# counter_module.net
KiCad netlist of a schematic drawn in EAGLE
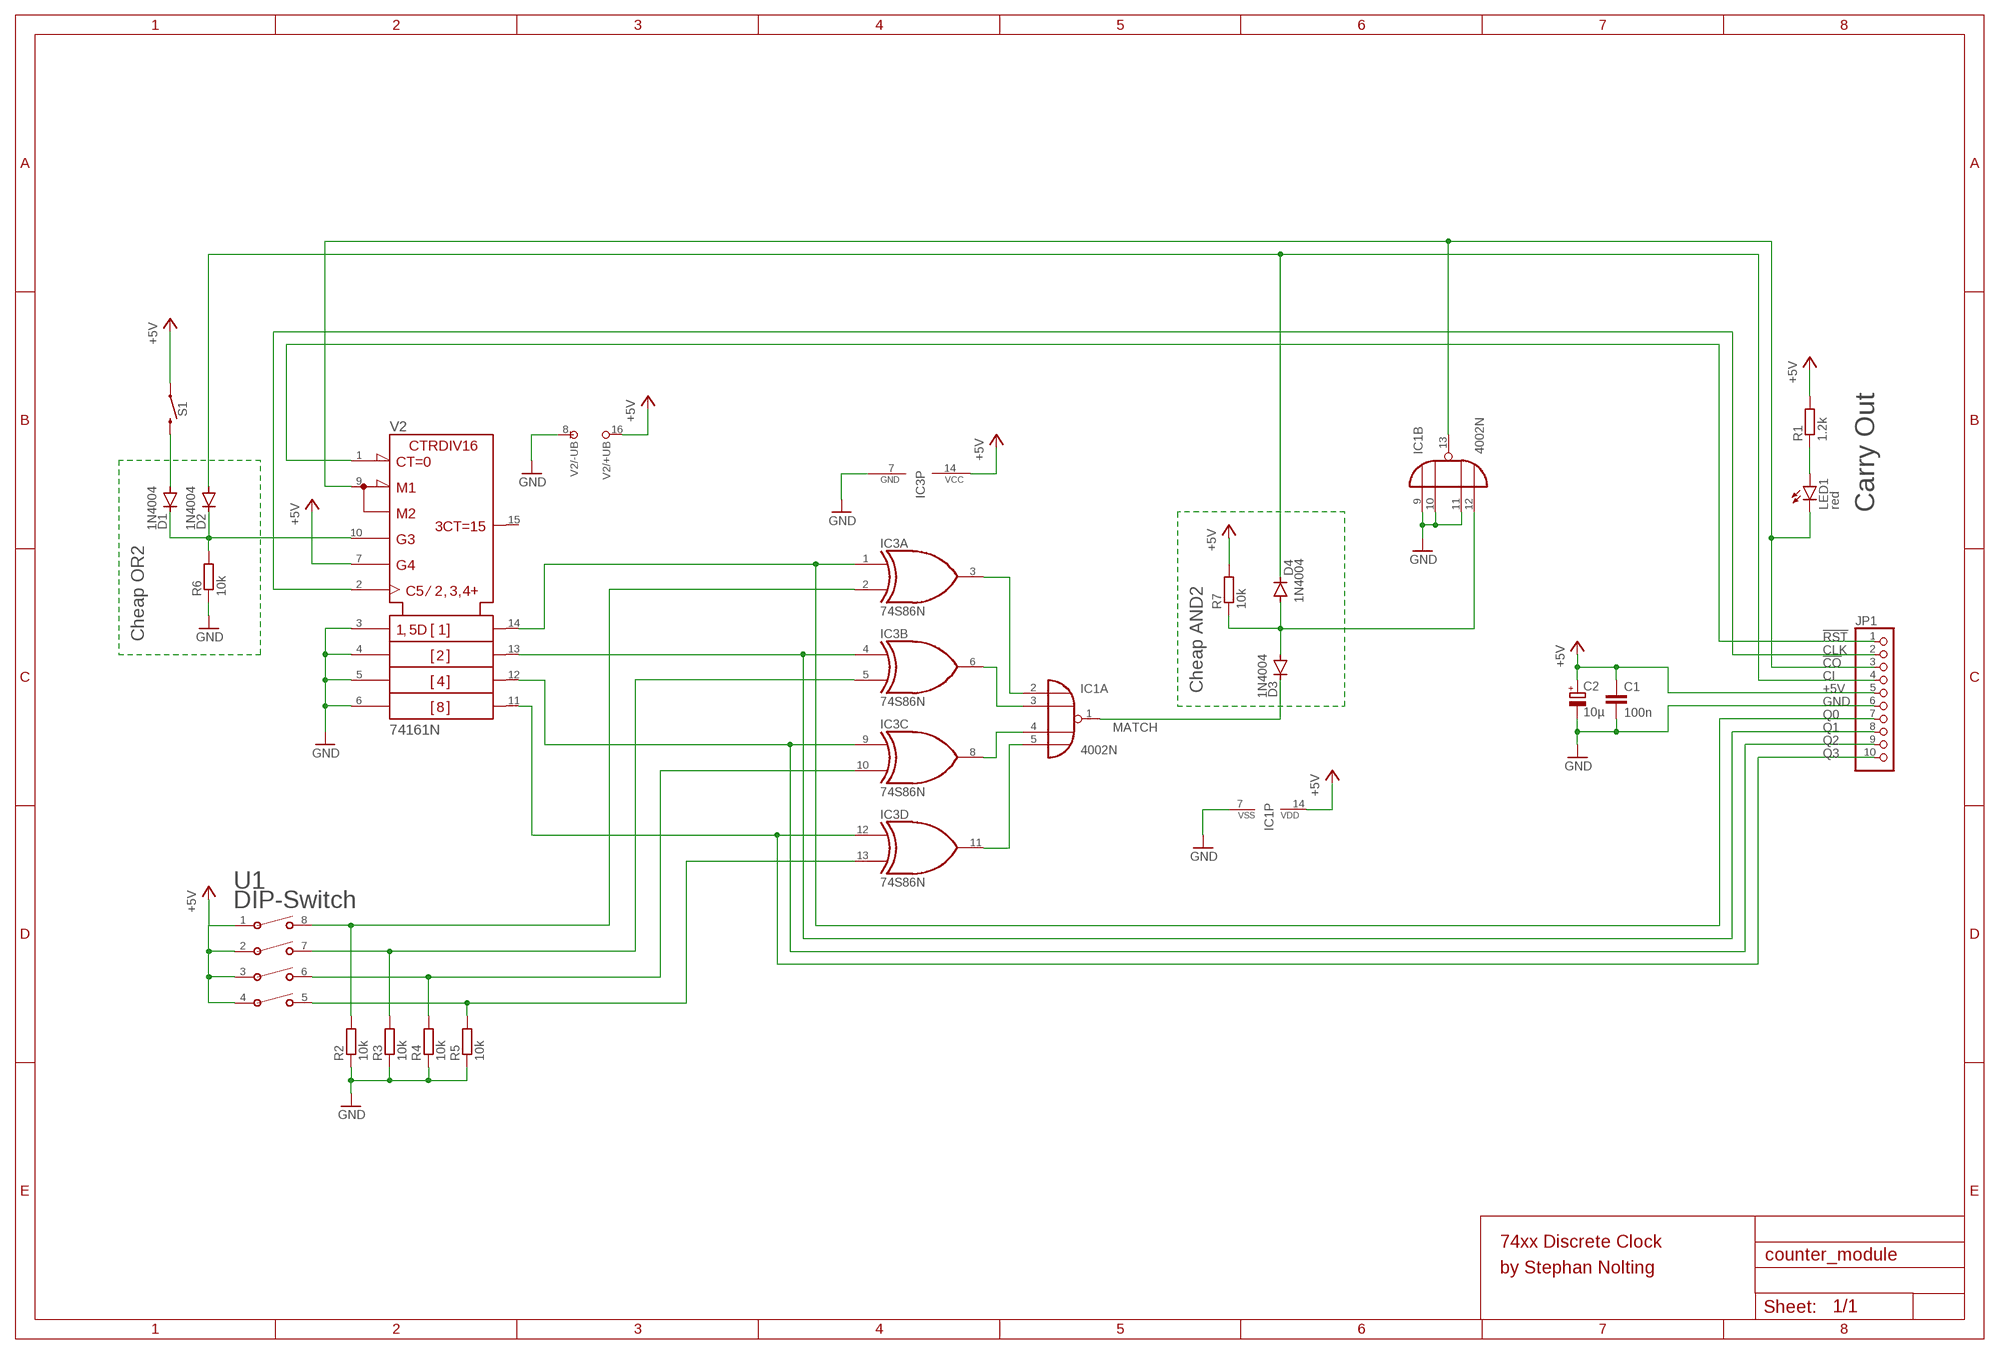
[diagram p0: schematic, sheet 1]

(export (version "E")
  (design (tool "Eeschema 10.0.6"))
  (components
    (comp (ref "C1")
      (value "100n")
      (footprint "eagle-import:C025-024X044")
      (libsource (lib "eagle-import") (part "C-EU025-024X044"))
    )
    (comp (ref "C2")
      (value "10µ")
      (footprint "eagle-import:E2-5")
      (libsource (lib "eagle-import") (part "CPOL-EUE2-5"))
    )
    (comp (ref "D1")
      (value "1N4004")
      (footprint "eagle-import:DO-41")
      (fields
        (field (name "DIGIKEY_PART_NUMBER") "1N4004MSCT-ND")
        (field (name "MANUFACTURER") "Micro Commercial Co")
        (field (name "CREATED_BY") "PCBLayout.com")
      )
      (libsource (lib "eagle-import") (part "1N4004"))
    )
    (comp (ref "D2")
      (value "1N4004")
      (footprint "eagle-import:DO-41")
      (fields
        (field (name "DIGIKEY_PART_NUMBER") "1N4004MSCT-ND")
        (field (name "MANUFACTURER") "Micro Commercial Co")
        (field (name "CREATED_BY") "PCBLayout.com")
      )
      (libsource (lib "eagle-import") (part "1N4004"))
    )
    (comp (ref "D3")
      (value "1N4004")
      (footprint "eagle-import:DO-41")
      (fields
        (field (name "DIGIKEY_PART_NUMBER") "1N4004MSCT-ND")
        (field (name "MANUFACTURER") "Micro Commercial Co")
        (field (name "CREATED_BY") "PCBLayout.com")
      )
      (libsource (lib "eagle-import") (part "1N4004"))
    )
    (comp (ref "D4")
      (value "1N4004")
      (footprint "eagle-import:DO-41")
      (fields
        (field (name "DIGIKEY_PART_NUMBER") "1N4004MSCT-ND")
        (field (name "MANUFACTURER") "Micro Commercial Co")
        (field (name "CREATED_BY") "PCBLayout.com")
      )
      (libsource (lib "eagle-import") (part "1N4004"))
    )
    (comp (ref "IC1")
      (value "4002N")
      (footprint "eagle-import:DIL14")
      (libsource (lib "eagle-import") (part "4002N"))
    )
    (comp (ref "IC3")
      (value "74S86N")
      (footprint "eagle-import:DIL14")
      (libsource (lib "eagle-import") (part "7486NS"))
    )
    (comp (ref "JP1")
      (value "PINHD-1X10/90")
      (footprint "eagle-import:1X10_90")
      (libsource (lib "eagle-import") (part "PINHD-1X10/90"))
    )
    (comp (ref "LED1")
      (value "red")
      (footprint "eagle-import:LED3MM")
      (libsource (lib "eagle-import") (part "LED3MM"))
    )
    (comp (ref "R1")
      (value "1.2k")
      (footprint "eagle-import:0204_7")
      (libsource (lib "eagle-import") (part "R-EU_0204/7"))
    )
    (comp (ref "R2")
      (value "10k")
      (footprint "eagle-import:0204_7")
      (libsource (lib "eagle-import") (part "R-EU_0204/7"))
    )
    (comp (ref "R3")
      (value "10k")
      (footprint "eagle-import:0204_7")
      (libsource (lib "eagle-import") (part "R-EU_0204/7"))
    )
    (comp (ref "R4")
      (value "10k")
      (footprint "eagle-import:0204_7")
      (libsource (lib "eagle-import") (part "R-EU_0204/7"))
    )
    (comp (ref "R5")
      (value "10k")
      (footprint "eagle-import:0204_7")
      (libsource (lib "eagle-import") (part "R-EU_0204/7"))
    )
    (comp (ref "R6")
      (value "10k")
      (footprint "eagle-import:0204_7")
      (libsource (lib "eagle-import") (part "R-EU_0204/7"))
    )
    (comp (ref "R7")
      (value "10k")
      (footprint "eagle-import:0204_7")
      (libsource (lib "eagle-import") (part "R-EU_0204/7"))
    )
    (comp (ref "S1")
      (value "MOMENTARY-SWITCH-SPST-PTH-RIGHT-ANGLE-KIT")
      (footprint "eagle-import:TACTILE_SWITCH_PTH_RIGHT_ANGLE_KIT")
      (libsource (lib "eagle-import") (part "MOMENTARY-SWITCH-SPST-PTH-RIGHT-ANGLE-KIT"))
    )
    (comp (ref "U1")
      (value "DIP-Switch")
      (footprint "eagle-import:SWDIP8_315X360P100")
      (fields
        (field (name "MANUFACTURER_PART_NUMBER") "3-5435640-5")
        (field (name "COPYRIGHT") "Copyright (C) 2016 Accelerated Designs. All rights reserved")
      )
      (libsource (lib "eagle-import") (part "3-5435640-5"))
    )
    (comp (ref "V2")
      (value "74161N")
      (footprint "eagle-import:DIL16")
      (libsource (lib "eagle-import") (part "74161N"))
    )
  )
  (nets
    (net (code "1") (name "+5V") (class "Default")
      (node (ref "C1") (pin "1") (pinfunction "1_1") (pintype "passive"))
      (node (ref "C2") (pin "+") (pinfunction "+_+") (pintype "passive"))
      (node (ref "IC1") (pin "14") (pinfunction "VDD_14") (pintype "power_in"))
      (node (ref "IC3") (pin "14") (pinfunction "VCC_14") (pintype "power_in"))
      (node (ref "JP1") (pin "5") (pinfunction "5_5") (pintype "passive"))
      (node (ref "R1") (pin "2") (pinfunction "2_2") (pintype "passive"))
      (node (ref "R7") (pin "2") (pinfunction "2_2") (pintype "passive"))
      (node (ref "S1") (pin "1") (pinfunction "1_1") (pintype "passive"))
      (node (ref "U1") (pin "1") (pinfunction "1_1") (pintype "passive"))
      (node (ref "U1") (pin "2") (pinfunction "2_2") (pintype "passive"))
      (node (ref "U1") (pin "3") (pinfunction "3_3") (pintype "passive"))
      (node (ref "U1") (pin "4") (pinfunction "4_4") (pintype "passive"))
      (node (ref "V2") (pin "16") (pinfunction "+UB_16") (pintype "power_in"))
      (node (ref "V2") (pin "7") (pinfunction "ENP_7") (pintype "input"))
    )
    (net (code "2") (name "/CI") (class "Default")
      (node (ref "D2") (pin "A") (pinfunction "A_A") (pintype "passive"))
      (node (ref "D4") (pin "C") (pinfunction "C_C") (pintype "passive"))
      (node (ref "JP1") (pin "4") (pinfunction "4_4") (pintype "passive"))
    )
    (net (code "3") (name "/CLK") (class "Default")
      (node (ref "JP1") (pin "2") (pinfunction "2_2") (pintype "passive"))
      (node (ref "V2") (pin "2") (pinfunction "CLK_2") (pintype "input"))
    )
    (net (code "4") (name "/MATCH") (class "Default")
      (node (ref "D3") (pin "C") (pinfunction "C_C") (pintype "passive"))
      (node (ref "IC1") (pin "1") (pinfunction "O_1") (pintype "output"))
    )
    (net (code "5") (name "/Q0") (class "Default")
      (node (ref "IC3") (pin "1") (pinfunction "I0_1") (pintype "input"))
      (node (ref "JP1") (pin "7") (pinfunction "7_7") (pintype "passive"))
      (node (ref "V2") (pin "14") (pinfunction "QA_14") (pintype "output"))
    )
    (net (code "6") (name "/Q1") (class "Default")
      (node (ref "IC3") (pin "4") (pinfunction "I0_4") (pintype "input"))
      (node (ref "JP1") (pin "8") (pinfunction "8_8") (pintype "passive"))
      (node (ref "V2") (pin "13") (pinfunction "QB_13") (pintype "output"))
    )
    (net (code "7") (name "/Q2") (class "Default")
      (node (ref "IC3") (pin "9") (pinfunction "I0_9") (pintype "input"))
      (node (ref "JP1") (pin "9") (pinfunction "9_9") (pintype "passive"))
      (node (ref "V2") (pin "12") (pinfunction "QC_12") (pintype "output"))
    )
    (net (code "8") (name "/Q3") (class "Default")
      (node (ref "IC3") (pin "12") (pinfunction "I0_12") (pintype "input"))
      (node (ref "JP1") (pin "10") (pinfunction "10_10") (pintype "passive"))
      (node (ref "V2") (pin "11") (pinfunction "QD_11") (pintype "output"))
    )
    (net (code "9") (name "/~{CO}") (class "Default")
      (node (ref "IC1") (pin "13") (pinfunction "O_13") (pintype "output"))
      (node (ref "JP1") (pin "3") (pinfunction "3_3") (pintype "passive"))
      (node (ref "LED1") (pin "K") (pinfunction "C_K") (pintype "passive"))
      (node (ref "V2") (pin "9") (pinfunction "~{LOAD}_9") (pintype "input"))
    )
    (net (code "10") (name "/~{RST}") (class "Default")
      (node (ref "JP1") (pin "1") (pinfunction "1_1") (pintype "passive"))
      (node (ref "V2") (pin "1") (pinfunction "~{CLR}_1") (pintype "input"))
    )
    (net (code "11") (name "GND") (class "Default")
      (node (ref "C1") (pin "2") (pinfunction "2_2") (pintype "passive"))
      (node (ref "C2") (pin "-") (pinfunction "-_-") (pintype "passive"))
      (node (ref "IC1") (pin "10") (pinfunction "I1_10") (pintype "input"))
      (node (ref "IC1") (pin "11") (pinfunction "I2_11") (pintype "input"))
      (node (ref "IC1") (pin "7") (pinfunction "VSS_7") (pintype "power_in"))
      (node (ref "IC1") (pin "9") (pinfunction "I0_9") (pintype "input"))
      (node (ref "IC3") (pin "7") (pinfunction "GND_7") (pintype "power_in"))
      (node (ref "JP1") (pin "6") (pinfunction "6_6") (pintype "passive"))
      (node (ref "R2") (pin "1") (pinfunction "1_1") (pintype "passive"))
      (node (ref "R3") (pin "1") (pinfunction "1_1") (pintype "passive"))
      (node (ref "R4") (pin "1") (pinfunction "1_1") (pintype "passive"))
      (node (ref "R5") (pin "1") (pinfunction "1_1") (pintype "passive"))
      (node (ref "R6") (pin "1") (pinfunction "1_1") (pintype "passive"))
      (node (ref "V2") (pin "3") (pinfunction "A_3") (pintype "input"))
      (node (ref "V2") (pin "4") (pinfunction "B_4") (pintype "input"))
      (node (ref "V2") (pin "5") (pinfunction "C_5") (pintype "input"))
      (node (ref "V2") (pin "6") (pinfunction "D_6") (pintype "input"))
      (node (ref "V2") (pin "8") (pinfunction "-UB_8") (pintype "power_in"))
    )
    (net (code "12") (name "Net-(D1-PadA)") (class "Default")
      (node (ref "D1") (pin "A") (pinfunction "A_A") (pintype "passive"))
      (node (ref "S1") (pin "2") (pinfunction "2_2") (pintype "passive"))
    )
    (net (code "13") (name "Net-(IC1A-I0)") (class "Default")
      (node (ref "IC1") (pin "2") (pinfunction "I0_2") (pintype "input"))
      (node (ref "IC3") (pin "3") (pinfunction "O_3") (pintype "output"))
    )
    (net (code "14") (name "Net-(IC1A-I1)") (class "Default")
      (node (ref "IC1") (pin "3") (pinfunction "I1_3") (pintype "input"))
      (node (ref "IC3") (pin "6") (pinfunction "O_6") (pintype "output"))
    )
    (net (code "15") (name "Net-(IC1A-I2)") (class "Default")
      (node (ref "IC1") (pin "4") (pinfunction "I2_4") (pintype "input"))
      (node (ref "IC3") (pin "8") (pinfunction "O_8") (pintype "output"))
    )
    (net (code "16") (name "Net-(IC1A-I3)") (class "Default")
      (node (ref "IC1") (pin "5") (pinfunction "I3_5") (pintype "input"))
      (node (ref "IC3") (pin "11") (pinfunction "O_11") (pintype "output"))
    )
    (net (code "17") (name "Net-(IC1B-I3)") (class "Default")
      (node (ref "D3") (pin "A") (pinfunction "A_A") (pintype "passive"))
      (node (ref "D4") (pin "A") (pinfunction "A_A") (pintype "passive"))
      (node (ref "IC1") (pin "12") (pinfunction "I3_12") (pintype "input"))
      (node (ref "R7") (pin "1") (pinfunction "1_1") (pintype "passive"))
    )
    (net (code "18") (name "Net-(IC3A-I1)") (class "Default")
      (node (ref "IC3") (pin "2") (pinfunction "I1_2") (pintype "input"))
      (node (ref "R2") (pin "2") (pinfunction "2_2") (pintype "passive"))
      (node (ref "U1") (pin "8") (pinfunction "8_8") (pintype "passive"))
    )
    (net (code "19") (name "Net-(IC3B-I1)") (class "Default")
      (node (ref "IC3") (pin "5") (pinfunction "I1_5") (pintype "input"))
      (node (ref "R3") (pin "2") (pinfunction "2_2") (pintype "passive"))
      (node (ref "U1") (pin "7") (pinfunction "7_7") (pintype "passive"))
    )
    (net (code "20") (name "Net-(IC3C-I1)") (class "Default")
      (node (ref "IC3") (pin "10") (pinfunction "I1_10") (pintype "input"))
      (node (ref "R4") (pin "2") (pinfunction "2_2") (pintype "passive"))
      (node (ref "U1") (pin "6") (pinfunction "6_6") (pintype "passive"))
    )
    (net (code "21") (name "Net-(IC3D-I1)") (class "Default")
      (node (ref "IC3") (pin "13") (pinfunction "I1_13") (pintype "input"))
      (node (ref "R5") (pin "2") (pinfunction "2_2") (pintype "passive"))
      (node (ref "U1") (pin "5") (pinfunction "5_5") (pintype "passive"))
    )
    (net (code "22") (name "Net-(LED1-PadA)") (class "Default")
      (node (ref "LED1") (pin "A") (pinfunction "A_A") (pintype "passive"))
      (node (ref "R1") (pin "1") (pinfunction "1_1") (pintype "passive"))
    )
    (net (code "23") (name "Net-(V2C-ENT)") (class "Default")
      (node (ref "D1") (pin "C") (pinfunction "C_C") (pintype "passive"))
      (node (ref "D2") (pin "C") (pinfunction "C_C") (pintype "passive"))
      (node (ref "R6") (pin "2") (pinfunction "2_2") (pintype "passive"))
      (node (ref "V2") (pin "10") (pinfunction "ENT_10") (pintype "input"))
    )
    (net (code "24") (name "unconnected-(V2C-RCO-Pad15)") (class "Default")
      (node (ref "V2") (pin "15") (pinfunction "RCO_15") (pintype "output"))
    )
  )
)
